# qo-100-psu-interface.net
KiCad netlist of a schematic drawn in EAGLE
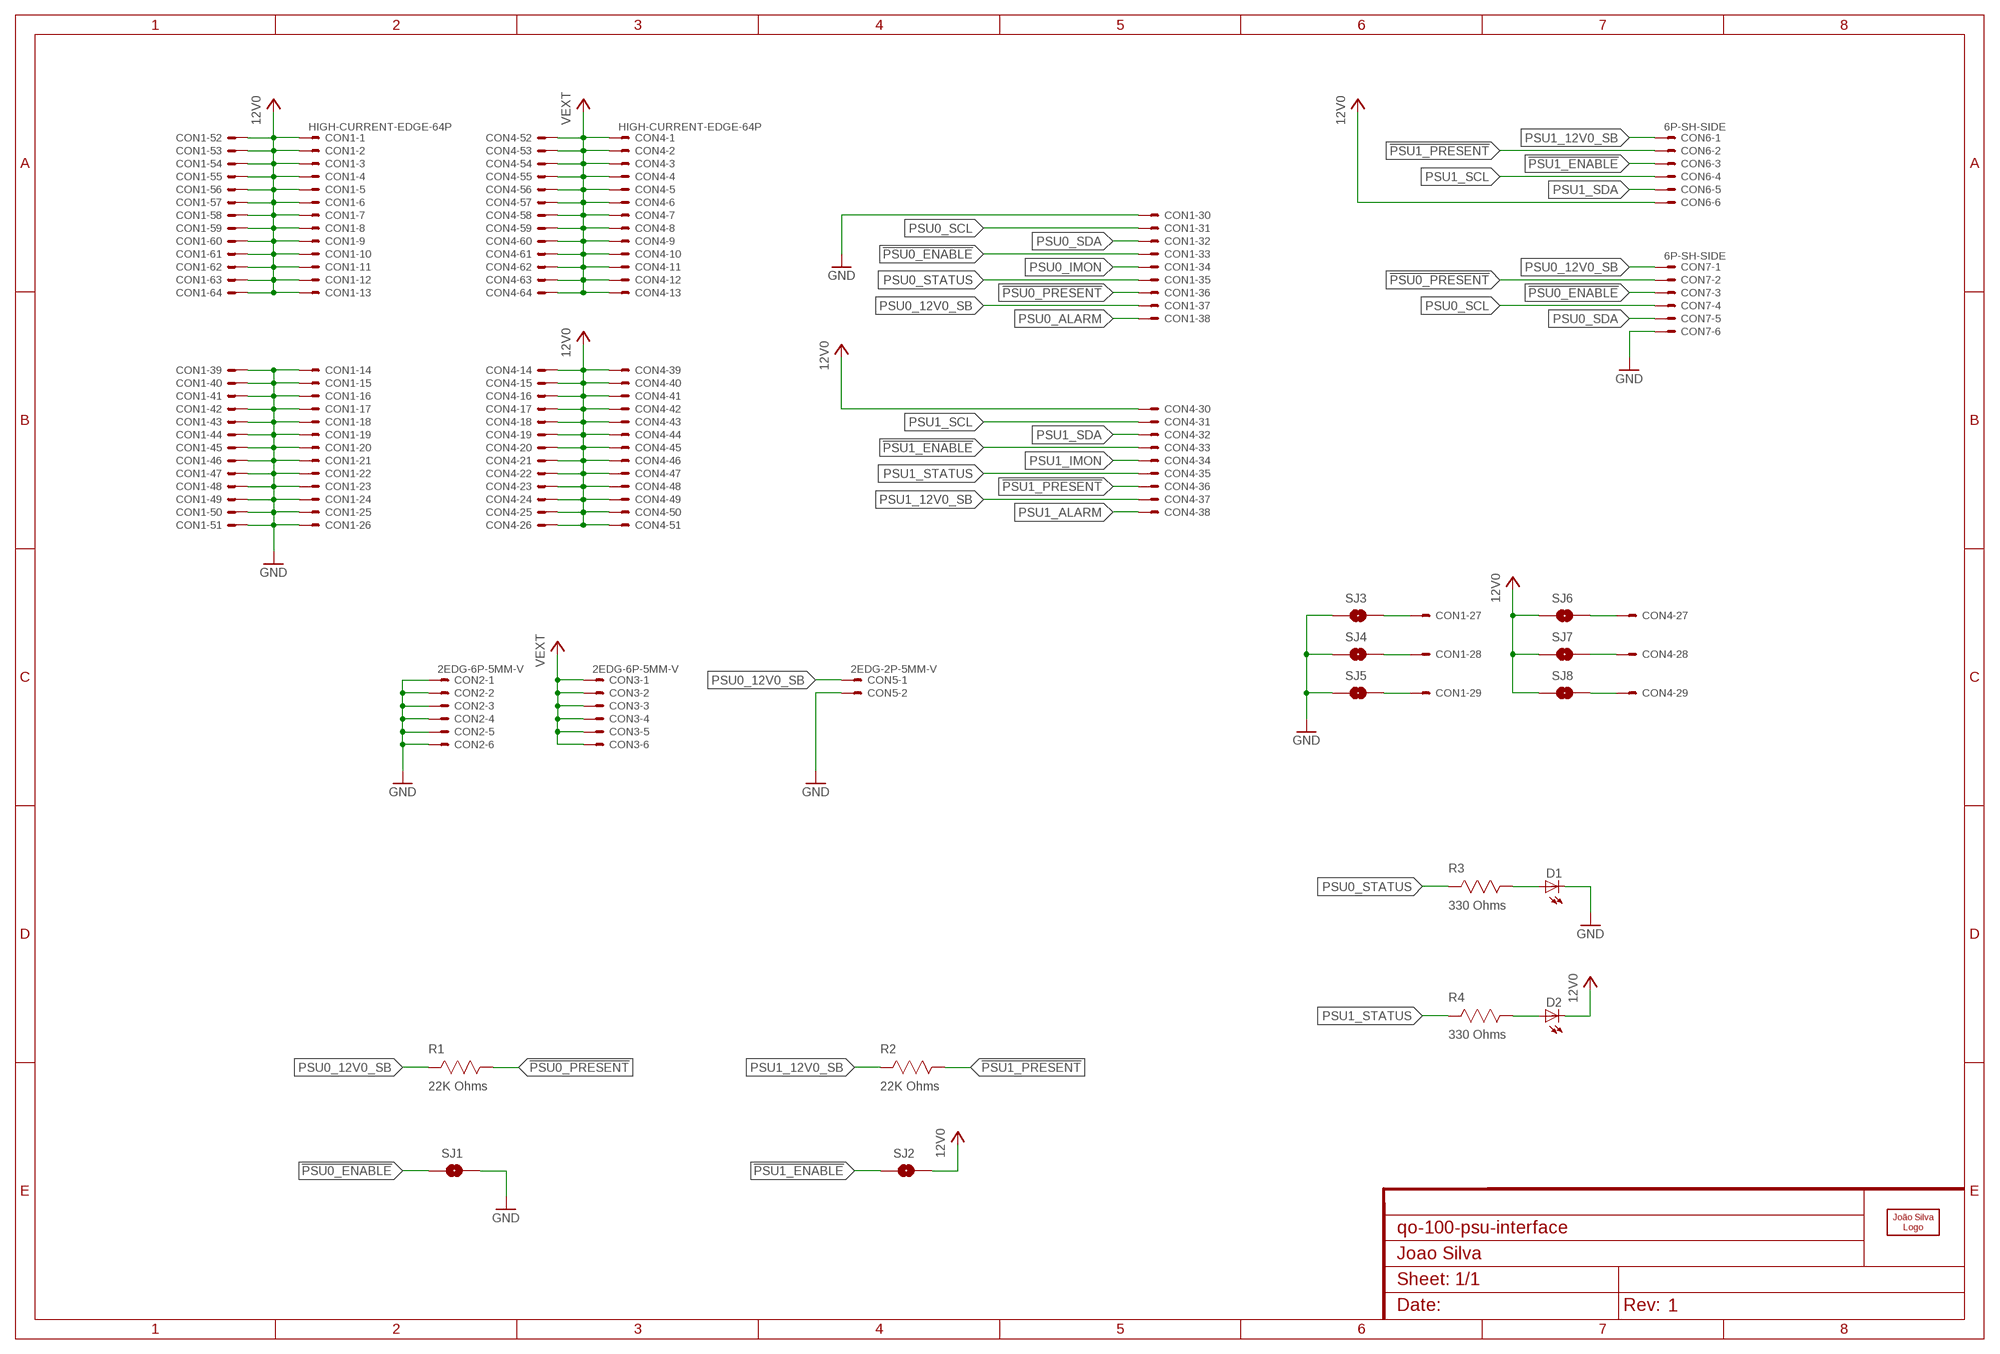
[diagram p0: schematic, sheet 1]

(export (version "E")
  (design (tool "Eeschema 10.0.6"))
  (components
    (comp (ref "CON1")
      (value "HIGH-CURRENT-EDGE-64P")
      (footprint "eagle-import:HIGH-CURRENT-EDGE-64P")
      (libsource (lib "eagle-import") (part "HIGH-CURRENT-EDGE-64P"))
    )
    (comp (ref "CON2")
      (value "2EDG-6P-5MM-V")
      (footprint "eagle-import:2EDG-6P-5MM-V")
      (libsource (lib "eagle-import") (part "2EDG-6P-5MM-V"))
    )
    (comp (ref "CON3")
      (value "2EDG-6P-5MM-V")
      (footprint "eagle-import:2EDG-6P-5MM-V")
      (libsource (lib "eagle-import") (part "2EDG-6P-5MM-V"))
    )
    (comp (ref "CON4")
      (value "HIGH-CURRENT-EDGE-64P")
      (footprint "eagle-import:HIGH-CURRENT-EDGE-64P")
      (libsource (lib "eagle-import") (part "HIGH-CURRENT-EDGE-64P"))
    )
    (comp (ref "CON5")
      (value "2EDG-2P-5MM-V")
      (footprint "eagle-import:2EDG-2P-5MM-V")
      (libsource (lib "eagle-import") (part "2EDG-2P-5MM-V"))
    )
    (comp (ref "CON6")
      (value "6P-SH-SIDE")
      (footprint "eagle-import:SH-06-SIDE")
      (libsource (lib "eagle-import") (part "6P-SH-SIDE"))
    )
    (comp (ref "CON7")
      (value "6P-SH-SIDE")
      (footprint "eagle-import:SH-06-SIDE")
      (libsource (lib "eagle-import") (part "6P-SH-SIDE"))
    )
    (comp (ref "D1")
      (value "LED0603")
      (footprint "eagle-import:0603")
      (libsource (lib "eagle-import") (part "LED0603"))
    )
    (comp (ref "D2")
      (value "LED0603")
      (footprint "eagle-import:0603")
      (libsource (lib "eagle-import") (part "LED0603"))
    )
    (comp (ref "LOGO1")
      (value "JS-5MM")
      (footprint "eagle-import:JS_5MM")
      (libsource (lib "eagle-import") (part "JS-5MM"))
    )
    (comp (ref "R1")
      (value "22K Ohms")
      (footprint "eagle-import:RES0603")
      (libsource (lib "eagle-import") (part "RESISTOR-0603"))
    )
    (comp (ref "R2")
      (value "22K Ohms")
      (footprint "eagle-import:RES0603")
      (libsource (lib "eagle-import") (part "RESISTOR-0603"))
    )
    (comp (ref "R3")
      (value "330 Ohms")
      (footprint "eagle-import:RES0603")
      (libsource (lib "eagle-import") (part "RESISTOR-0603"))
    )
    (comp (ref "R4")
      (value "330 Ohms")
      (footprint "eagle-import:RES0603")
      (libsource (lib "eagle-import") (part "RESISTOR-0603"))
    )
    (comp (ref "SJ1")
      (value "SJS")
      (footprint "eagle-import:SJ_S")
      (libsource (lib "eagle-import") (part "SJS"))
    )
    (comp (ref "SJ2")
      (value "SJS")
      (footprint "eagle-import:SJ_S")
      (libsource (lib "eagle-import") (part "SJS"))
    )
    (comp (ref "SJ3")
      (value "SJS")
      (footprint "eagle-import:SJ_S")
      (libsource (lib "eagle-import") (part "SJS"))
    )
    (comp (ref "SJ4")
      (value "SJS")
      (footprint "eagle-import:SJ_S")
      (libsource (lib "eagle-import") (part "SJS"))
    )
    (comp (ref "SJ5")
      (value "SJS")
      (footprint "eagle-import:SJ_S")
      (libsource (lib "eagle-import") (part "SJS"))
    )
    (comp (ref "SJ6")
      (value "SJS")
      (footprint "eagle-import:SJ_S")
      (libsource (lib "eagle-import") (part "SJS"))
    )
    (comp (ref "SJ7")
      (value "SJS")
      (footprint "eagle-import:SJ_S")
      (libsource (lib "eagle-import") (part "SJS"))
    )
    (comp (ref "SJ8")
      (value "SJS")
      (footprint "eagle-import:SJ_S")
      (libsource (lib "eagle-import") (part "SJS"))
    )
  )
  (nets
    (net (code "1") (name "/~{PSU0_ENABLE}") (class "Default")
      (node (ref "CON1") (pin "33") (pinfunction "S_33") (pintype "passive"))
      (node (ref "CON7") (pin "3") (pinfunction "S_3") (pintype "passive"))
      (node (ref "SJ1") (pin "1") (pinfunction "1_1") (pintype "passive"))
    )
    (net (code "2") (name "/~{PSU0_PRESENT}") (class "Default")
      (node (ref "CON1") (pin "36") (pinfunction "S_36") (pintype "passive"))
      (node (ref "CON7") (pin "2") (pinfunction "S_2") (pintype "passive"))
      (node (ref "R1") (pin "1") (pinfunction "1_1") (pintype "passive"))
    )
    (net (code "3") (name "/~{PSU1_ENABLE}") (class "Default")
      (node (ref "CON4") (pin "33") (pinfunction "S_33") (pintype "passive"))
      (node (ref "CON6") (pin "3") (pinfunction "S_3") (pintype "passive"))
      (node (ref "SJ2") (pin "1") (pinfunction "1_1") (pintype "passive"))
    )
    (net (code "4") (name "/~{PSU1_PRESENT}") (class "Default")
      (node (ref "CON4") (pin "36") (pinfunction "S_36") (pintype "passive"))
      (node (ref "CON6") (pin "2") (pinfunction "S_2") (pintype "passive"))
      (node (ref "R2") (pin "1") (pinfunction "1_1") (pintype "passive"))
    )
    (net (code "5") (name "12V0") (class "Default")
      (node (ref "CON1") (pin "1") (pinfunction "S_1") (pintype "passive"))
      (node (ref "CON1") (pin "10") (pinfunction "S_10") (pintype "passive"))
      (node (ref "CON1") (pin "11") (pinfunction "S_11") (pintype "passive"))
      (node (ref "CON1") (pin "12") (pinfunction "S_12") (pintype "passive"))
      (node (ref "CON1") (pin "13") (pinfunction "S_13") (pintype "passive"))
      (node (ref "CON1") (pin "2") (pinfunction "S_2") (pintype "passive"))
      (node (ref "CON1") (pin "3") (pinfunction "S_3") (pintype "passive"))
      (node (ref "CON1") (pin "4") (pinfunction "S_4") (pintype "passive"))
      (node (ref "CON1") (pin "5") (pinfunction "S_5") (pintype "passive"))
      (node (ref "CON1") (pin "52") (pinfunction "S_52") (pintype "passive"))
      (node (ref "CON1") (pin "53") (pinfunction "S_53") (pintype "passive"))
      (node (ref "CON1") (pin "54") (pinfunction "S_54") (pintype "passive"))
      (node (ref "CON1") (pin "55") (pinfunction "S_55") (pintype "passive"))
      (node (ref "CON1") (pin "56") (pinfunction "S_56") (pintype "passive"))
      (node (ref "CON1") (pin "57") (pinfunction "S_57") (pintype "passive"))
      (node (ref "CON1") (pin "58") (pinfunction "S_58") (pintype "passive"))
      (node (ref "CON1") (pin "59") (pinfunction "S_59") (pintype "passive"))
      (node (ref "CON1") (pin "6") (pinfunction "S_6") (pintype "passive"))
      (node (ref "CON1") (pin "60") (pinfunction "S_60") (pintype "passive"))
      (node (ref "CON1") (pin "61") (pinfunction "S_61") (pintype "passive"))
      (node (ref "CON1") (pin "62") (pinfunction "S_62") (pintype "passive"))
      (node (ref "CON1") (pin "63") (pinfunction "S_63") (pintype "passive"))
      (node (ref "CON1") (pin "64") (pinfunction "S_64") (pintype "passive"))
      (node (ref "CON1") (pin "7") (pinfunction "S_7") (pintype "passive"))
      (node (ref "CON1") (pin "8") (pinfunction "S_8") (pintype "passive"))
      (node (ref "CON1") (pin "9") (pinfunction "S_9") (pintype "passive"))
      (node (ref "CON4") (pin "14") (pinfunction "S_14") (pintype "passive"))
      (node (ref "CON4") (pin "15") (pinfunction "S_15") (pintype "passive"))
      (node (ref "CON4") (pin "16") (pinfunction "S_16") (pintype "passive"))
      (node (ref "CON4") (pin "17") (pinfunction "S_17") (pintype "passive"))
      (node (ref "CON4") (pin "18") (pinfunction "S_18") (pintype "passive"))
      (node (ref "CON4") (pin "19") (pinfunction "S_19") (pintype "passive"))
      (node (ref "CON4") (pin "20") (pinfunction "S_20") (pintype "passive"))
      (node (ref "CON4") (pin "21") (pinfunction "S_21") (pintype "passive"))
      (node (ref "CON4") (pin "22") (pinfunction "S_22") (pintype "passive"))
      (node (ref "CON4") (pin "23") (pinfunction "S_23") (pintype "passive"))
      (node (ref "CON4") (pin "24") (pinfunction "S_24") (pintype "passive"))
      (node (ref "CON4") (pin "25") (pinfunction "S_25") (pintype "passive"))
      (node (ref "CON4") (pin "26") (pinfunction "S_26") (pintype "passive"))
      (node (ref "CON4") (pin "30") (pinfunction "S_30") (pintype "passive"))
      (node (ref "CON4") (pin "39") (pinfunction "S_39") (pintype "passive"))
      (node (ref "CON4") (pin "40") (pinfunction "S_40") (pintype "passive"))
      (node (ref "CON4") (pin "41") (pinfunction "S_41") (pintype "passive"))
      (node (ref "CON4") (pin "42") (pinfunction "S_42") (pintype "passive"))
      (node (ref "CON4") (pin "43") (pinfunction "S_43") (pintype "passive"))
      (node (ref "CON4") (pin "44") (pinfunction "S_44") (pintype "passive"))
      (node (ref "CON4") (pin "45") (pinfunction "S_45") (pintype "passive"))
      (node (ref "CON4") (pin "46") (pinfunction "S_46") (pintype "passive"))
      (node (ref "CON4") (pin "47") (pinfunction "S_47") (pintype "passive"))
      (node (ref "CON4") (pin "48") (pinfunction "S_48") (pintype "passive"))
      (node (ref "CON4") (pin "49") (pinfunction "S_49") (pintype "passive"))
      (node (ref "CON4") (pin "50") (pinfunction "S_50") (pintype "passive"))
      (node (ref "CON4") (pin "51") (pinfunction "S_51") (pintype "passive"))
      (node (ref "CON6") (pin "6") (pinfunction "S_6") (pintype "passive"))
      (node (ref "D2") (pin "C") (pinfunction "C_C") (pintype "passive"))
      (node (ref "SJ2") (pin "2") (pinfunction "2_2") (pintype "passive"))
      (node (ref "SJ6") (pin "1") (pinfunction "1_1") (pintype "passive"))
      (node (ref "SJ7") (pin "1") (pinfunction "1_1") (pintype "passive"))
      (node (ref "SJ8") (pin "1") (pinfunction "1_1") (pintype "passive"))
    )
    (net (code "6") (name "GND") (class "Default")
      (node (ref "CON1") (pin "14") (pinfunction "S_14") (pintype "passive"))
      (node (ref "CON1") (pin "15") (pinfunction "S_15") (pintype "passive"))
      (node (ref "CON1") (pin "16") (pinfunction "S_16") (pintype "passive"))
      (node (ref "CON1") (pin "17") (pinfunction "S_17") (pintype "passive"))
      (node (ref "CON1") (pin "18") (pinfunction "S_18") (pintype "passive"))
      (node (ref "CON1") (pin "19") (pinfunction "S_19") (pintype "passive"))
      (node (ref "CON1") (pin "20") (pinfunction "S_20") (pintype "passive"))
      (node (ref "CON1") (pin "21") (pinfunction "S_21") (pintype "passive"))
      (node (ref "CON1") (pin "22") (pinfunction "S_22") (pintype "passive"))
      (node (ref "CON1") (pin "23") (pinfunction "S_23") (pintype "passive"))
      (node (ref "CON1") (pin "24") (pinfunction "S_24") (pintype "passive"))
      (node (ref "CON1") (pin "25") (pinfunction "S_25") (pintype "passive"))
      (node (ref "CON1") (pin "26") (pinfunction "S_26") (pintype "passive"))
      (node (ref "CON1") (pin "30") (pinfunction "S_30") (pintype "passive"))
      (node (ref "CON1") (pin "39") (pinfunction "S_39") (pintype "passive"))
      (node (ref "CON1") (pin "40") (pinfunction "S_40") (pintype "passive"))
      (node (ref "CON1") (pin "41") (pinfunction "S_41") (pintype "passive"))
      (node (ref "CON1") (pin "42") (pinfunction "S_42") (pintype "passive"))
      (node (ref "CON1") (pin "43") (pinfunction "S_43") (pintype "passive"))
      (node (ref "CON1") (pin "44") (pinfunction "S_44") (pintype "passive"))
      (node (ref "CON1") (pin "45") (pinfunction "S_45") (pintype "passive"))
      (node (ref "CON1") (pin "46") (pinfunction "S_46") (pintype "passive"))
      (node (ref "CON1") (pin "47") (pinfunction "S_47") (pintype "passive"))
      (node (ref "CON1") (pin "48") (pinfunction "S_48") (pintype "passive"))
      (node (ref "CON1") (pin "49") (pinfunction "S_49") (pintype "passive"))
      (node (ref "CON1") (pin "50") (pinfunction "S_50") (pintype "passive"))
      (node (ref "CON1") (pin "51") (pinfunction "S_51") (pintype "passive"))
      (node (ref "CON2") (pin "P$1") (pinfunction "S_P$1") (pintype "passive"))
      (node (ref "CON2") (pin "P$2") (pinfunction "S_P$2") (pintype "passive"))
      (node (ref "CON2") (pin "P$3") (pinfunction "S_P$3") (pintype "passive"))
      (node (ref "CON2") (pin "P$4") (pinfunction "S_P$4") (pintype "passive"))
      (node (ref "CON2") (pin "P$5") (pinfunction "S_P$5") (pintype "passive"))
      (node (ref "CON2") (pin "P$6") (pinfunction "S_P$6") (pintype "passive"))
      (node (ref "CON5") (pin "P$2") (pinfunction "S_P$2") (pintype "passive"))
      (node (ref "CON7") (pin "6") (pinfunction "S_6") (pintype "passive"))
      (node (ref "D1") (pin "C") (pinfunction "C_C") (pintype "passive"))
      (node (ref "SJ1") (pin "2") (pinfunction "2_2") (pintype "passive"))
      (node (ref "SJ3") (pin "1") (pinfunction "1_1") (pintype "passive"))
      (node (ref "SJ4") (pin "1") (pinfunction "1_1") (pintype "passive"))
      (node (ref "SJ5") (pin "1") (pinfunction "1_1") (pintype "passive"))
    )
    (net (code "7") (name "Net-(CON1T-S)") (class "Default")
      (node (ref "CON1") (pin "27") (pinfunction "S_27") (pintype "passive"))
      (node (ref "SJ3") (pin "2") (pinfunction "2_2") (pintype "passive"))
    )
    (net (code "8") (name "Net-(CON1U-S)") (class "Default")
      (node (ref "CON1") (pin "28") (pinfunction "S_28") (pintype "passive"))
      (node (ref "SJ4") (pin "2") (pinfunction "2_2") (pintype "passive"))
    )
    (net (code "9") (name "Net-(CON1V-S)") (class "Default")
      (node (ref "CON1") (pin "29") (pinfunction "S_29") (pintype "passive"))
      (node (ref "SJ5") (pin "2") (pinfunction "2_2") (pintype "passive"))
    )
    (net (code "10") (name "Net-(CON4T-S)") (class "Default")
      (node (ref "CON4") (pin "27") (pinfunction "S_27") (pintype "passive"))
      (node (ref "SJ6") (pin "2") (pinfunction "2_2") (pintype "passive"))
    )
    (net (code "11") (name "Net-(CON4U-S)") (class "Default")
      (node (ref "CON4") (pin "28") (pinfunction "S_28") (pintype "passive"))
      (node (ref "SJ7") (pin "2") (pinfunction "2_2") (pintype "passive"))
    )
    (net (code "12") (name "Net-(CON4V-S)") (class "Default")
      (node (ref "CON4") (pin "29") (pinfunction "S_29") (pintype "passive"))
      (node (ref "SJ8") (pin "2") (pinfunction "2_2") (pintype "passive"))
    )
    (net (code "13") (name "Net-(D1-PadA)") (class "Default")
      (node (ref "D1") (pin "A") (pinfunction "A_A") (pintype "passive"))
      (node (ref "R3") (pin "1") (pinfunction "1_1") (pintype "passive"))
    )
    (net (code "14") (name "Net-(D2-PadA)") (class "Default")
      (node (ref "D2") (pin "A") (pinfunction "A_A") (pintype "passive"))
      (node (ref "R4") (pin "1") (pinfunction "1_1") (pintype "passive"))
    )
    (net (code "15") (name "PSU0_12V0_SB") (class "Default")
      (node (ref "CON1") (pin "37") (pinfunction "S_37") (pintype "passive"))
      (node (ref "CON5") (pin "P$1") (pinfunction "S_P$1") (pintype "passive"))
      (node (ref "CON7") (pin "1") (pinfunction "S_1") (pintype "passive"))
      (node (ref "R1") (pin "2") (pinfunction "2_2") (pintype "passive"))
    )
    (net (code "16") (name "PSU0_ALARM") (class "Default")
      (node (ref "CON1") (pin "38") (pinfunction "S_38") (pintype "passive"))
    )
    (net (code "17") (name "PSU0_IMON") (class "Default")
      (node (ref "CON1") (pin "34") (pinfunction "S_34") (pintype "passive"))
    )
    (net (code "18") (name "PSU0_SCL") (class "Default")
      (node (ref "CON1") (pin "31") (pinfunction "S_31") (pintype "passive"))
      (node (ref "CON7") (pin "4") (pinfunction "S_4") (pintype "passive"))
    )
    (net (code "19") (name "PSU0_SDA") (class "Default")
      (node (ref "CON1") (pin "32") (pinfunction "S_32") (pintype "passive"))
      (node (ref "CON7") (pin "5") (pinfunction "S_5") (pintype "passive"))
    )
    (net (code "20") (name "PSU0_STATUS") (class "Default")
      (node (ref "CON1") (pin "35") (pinfunction "S_35") (pintype "passive"))
      (node (ref "R3") (pin "2") (pinfunction "2_2") (pintype "passive"))
    )
    (net (code "21") (name "PSU1_12V0_SB") (class "Default")
      (node (ref "CON4") (pin "37") (pinfunction "S_37") (pintype "passive"))
      (node (ref "CON6") (pin "1") (pinfunction "S_1") (pintype "passive"))
      (node (ref "R2") (pin "2") (pinfunction "2_2") (pintype "passive"))
    )
    (net (code "22") (name "PSU1_ALARM") (class "Default")
      (node (ref "CON4") (pin "38") (pinfunction "S_38") (pintype "passive"))
    )
    (net (code "23") (name "PSU1_IMON") (class "Default")
      (node (ref "CON4") (pin "34") (pinfunction "S_34") (pintype "passive"))
    )
    (net (code "24") (name "PSU1_SCL") (class "Default")
      (node (ref "CON4") (pin "31") (pinfunction "S_31") (pintype "passive"))
      (node (ref "CON6") (pin "4") (pinfunction "S_4") (pintype "passive"))
    )
    (net (code "25") (name "PSU1_SDA") (class "Default")
      (node (ref "CON4") (pin "32") (pinfunction "S_32") (pintype "passive"))
      (node (ref "CON6") (pin "5") (pinfunction "S_5") (pintype "passive"))
    )
    (net (code "26") (name "PSU1_STATUS") (class "Default")
      (node (ref "CON4") (pin "35") (pinfunction "S_35") (pintype "passive"))
      (node (ref "R4") (pin "2") (pinfunction "2_2") (pintype "passive"))
    )
    (net (code "27") (name "VEXT") (class "Default")
      (node (ref "CON3") (pin "P$1") (pinfunction "S_P$1") (pintype "passive"))
      (node (ref "CON3") (pin "P$2") (pinfunction "S_P$2") (pintype "passive"))
      (node (ref "CON3") (pin "P$3") (pinfunction "S_P$3") (pintype "passive"))
      (node (ref "CON3") (pin "P$4") (pinfunction "S_P$4") (pintype "passive"))
      (node (ref "CON3") (pin "P$5") (pinfunction "S_P$5") (pintype "passive"))
      (node (ref "CON3") (pin "P$6") (pinfunction "S_P$6") (pintype "passive"))
      (node (ref "CON4") (pin "1") (pinfunction "S_1") (pintype "passive"))
      (node (ref "CON4") (pin "10") (pinfunction "S_10") (pintype "passive"))
      (node (ref "CON4") (pin "11") (pinfunction "S_11") (pintype "passive"))
      (node (ref "CON4") (pin "12") (pinfunction "S_12") (pintype "passive"))
      (node (ref "CON4") (pin "13") (pinfunction "S_13") (pintype "passive"))
      (node (ref "CON4") (pin "2") (pinfunction "S_2") (pintype "passive"))
      (node (ref "CON4") (pin "3") (pinfunction "S_3") (pintype "passive"))
      (node (ref "CON4") (pin "4") (pinfunction "S_4") (pintype "passive"))
      (node (ref "CON4") (pin "5") (pinfunction "S_5") (pintype "passive"))
      (node (ref "CON4") (pin "52") (pinfunction "S_52") (pintype "passive"))
      (node (ref "CON4") (pin "53") (pinfunction "S_53") (pintype "passive"))
      (node (ref "CON4") (pin "54") (pinfunction "S_54") (pintype "passive"))
      (node (ref "CON4") (pin "55") (pinfunction "S_55") (pintype "passive"))
      (node (ref "CON4") (pin "56") (pinfunction "S_56") (pintype "passive"))
      (node (ref "CON4") (pin "57") (pinfunction "S_57") (pintype "passive"))
      (node (ref "CON4") (pin "58") (pinfunction "S_58") (pintype "passive"))
      (node (ref "CON4") (pin "59") (pinfunction "S_59") (pintype "passive"))
      (node (ref "CON4") (pin "6") (pinfunction "S_6") (pintype "passive"))
      (node (ref "CON4") (pin "60") (pinfunction "S_60") (pintype "passive"))
      (node (ref "CON4") (pin "61") (pinfunction "S_61") (pintype "passive"))
      (node (ref "CON4") (pin "62") (pinfunction "S_62") (pintype "passive"))
      (node (ref "CON4") (pin "63") (pinfunction "S_63") (pintype "passive"))
      (node (ref "CON4") (pin "64") (pinfunction "S_64") (pintype "passive"))
      (node (ref "CON4") (pin "7") (pinfunction "S_7") (pintype "passive"))
      (node (ref "CON4") (pin "8") (pinfunction "S_8") (pintype "passive"))
      (node (ref "CON4") (pin "9") (pinfunction "S_9") (pintype "passive"))
    )
  )
)
